# Mixer10_7M.net
KiCad netlist of a schematic drawn in Altium Designer
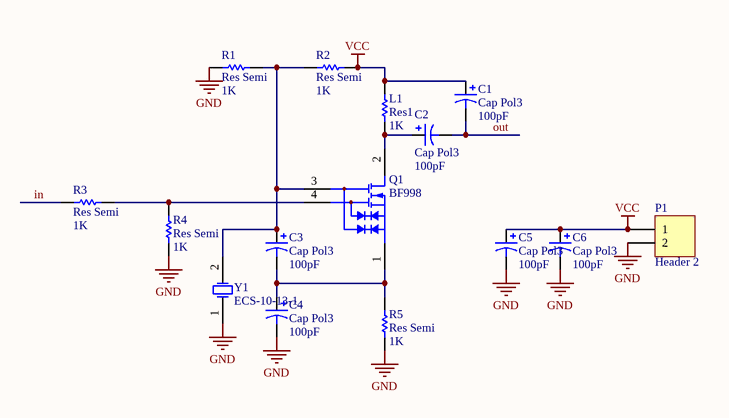
[diagram p0: Mixer10_7M.SchDoc]

(export (version "E")
  (design (tool "Eeschema 10.0.6"))
  (components
    (comp (ref "C1")
      (value "Cap Pol3")
      (footprint "C0805")
      (description "Polarized Capacitor (Surface Mount)")
      (fields (field (name "ALTIUM_VALUE") "100pF") (field (name "PUBLISHER") "Altium Limited"))
      (libsource (lib "Miscellaneous Devices") (part "Cap Pol3"))
    )
    (comp (ref "C2")
      (value "Cap Pol3")
      (footprint "C0805")
      (description "Polarized Capacitor (Surface Mount)")
      (fields (field (name "ALTIUM_VALUE") "100pF") (field (name "PUBLISHER") "Altium Limited"))
      (libsource (lib "Miscellaneous Devices") (part "Cap Pol3"))
    )
    (comp (ref "C3")
      (value "Cap Pol3")
      (footprint "C0805")
      (description "Polarized Capacitor (Surface Mount)")
      (fields (field (name "ALTIUM_VALUE") "100pF") (field (name "PUBLISHER") "Altium Limited"))
      (libsource (lib "Miscellaneous Devices") (part "Cap Pol3"))
    )
    (comp (ref "C4")
      (value "Cap Pol3")
      (footprint "C0805")
      (description "Polarized Capacitor (Surface Mount)")
      (fields (field (name "ALTIUM_VALUE") "100pF") (field (name "PUBLISHER") "Altium Limited"))
      (libsource (lib "Miscellaneous Devices") (part "Cap Pol3"))
    )
    (comp (ref "C5")
      (value "Cap Pol3")
      (footprint "C0805")
      (description "Polarized Capacitor (Surface Mount)")
      (fields (field (name "ALTIUM_VALUE") "100pF") (field (name "PUBLISHER") "Altium Limited"))
      (libsource (lib "Miscellaneous Devices") (part "Cap Pol3"))
    )
    (comp (ref "C6")
      (value "Cap Pol3")
      (footprint "C0805")
      (description "Polarized Capacitor (Surface Mount)")
      (fields (field (name "ALTIUM_VALUE") "100pF") (field (name "PUBLISHER") "Altium Limited"))
      (libsource (lib "Miscellaneous Devices") (part "Cap Pol3"))
    )
    (comp (ref "L1")
      (value "Res1")
      (footprint "AXIAL-0.3")
      (description "Resistor")
      (fields (field (name "ALTIUM_VALUE") "1K") (field (name "PUBLISHER") "Altium Limited"))
      (libsource (lib "Miscellaneous Devices") (part "Res1"))
    )
    (comp (ref "P1")
      (value "Header 2")
      (footprint "HDR1X2")
      (description "Header, 2-Pin")
      (fields (field (name "PUBLISHER") "Altium Limited"))
      (libsource (lib "Miscellaneous Connectors") (part "Header 2"))
    )
    (comp (ref "Q1")
      (value "BF998")
      (footprint "SOT143_N")
      (description "Silicon N-channel Dual-gate MOSFET")
      (fields (field (name "PUBLISHER") "Altium Limited"))
      (libsource (lib "Philips Discrete MOSFET - Low Power") (part "BF998"))
    )
    (comp (ref "R1")
      (value "Res Semi")
      (footprint "2012[0805]")
      (description "Semiconductor Resistor")
      (fields (field (name "ALTIUM_VALUE") "1K") (field (name "PUBLISHER") "Altium Limited"))
      (libsource (lib "Miscellaneous Devices") (part "Res Semi"))
    )
    (comp (ref "R2")
      (value "Res Semi")
      (footprint "2012[0805]")
      (description "Semiconductor Resistor")
      (fields (field (name "ALTIUM_VALUE") "1K") (field (name "PUBLISHER") "Altium Limited"))
      (libsource (lib "Miscellaneous Devices") (part "Res Semi"))
    )
    (comp (ref "R3")
      (value "Res Semi")
      (footprint "2012[0805]")
      (description "Semiconductor Resistor")
      (fields (field (name "ALTIUM_VALUE") "1K") (field (name "PUBLISHER") "Altium Limited"))
      (libsource (lib "Miscellaneous Devices") (part "Res Semi"))
    )
    (comp (ref "R4")
      (value "Res Semi")
      (footprint "2012[0805]")
      (description "Semiconductor Resistor")
      (fields (field (name "ALTIUM_VALUE") "1K") (field (name "PUBLISHER") "Altium Limited"))
      (libsource (lib "Miscellaneous Devices") (part "Res Semi"))
    )
    (comp (ref "R5")
      (value "Res Semi")
      (footprint "2012[0805]")
      (description "Semiconductor Resistor")
      (fields (field (name "ALTIUM_VALUE") "1K") (field (name "PUBLISHER") "Altium Limited"))
      (libsource (lib "Miscellaneous Devices") (part "Res Semi"))
    )
    (comp (ref "Y1")
      (value "ECS-10-13-1")
      (footprint "HC-49U")
      (description "Crystal Oscillator")
      (fields (field (name "PUBLISHER") "Altium Limited"))
      (libsource (lib "ECS Crystal Oscillator") (part "ECS-10-13-1"))
    )
  )
  (nets
    (net (code "1") (name "/in") (class "Default")
      (node (ref "R3") (pin "2") (pinfunction "2_2") (pintype "passive"))
    )
    (net (code "2") (name "/out") (class "Default")
      (node (ref "C1") (pin "2") (pinfunction "2_2") (pintype "passive"))
      (node (ref "C2") (pin "2") (pinfunction "2_2") (pintype "passive"))
    )
    (net (code "3") (name "GND") (class "Default")
      (node (ref "C4") (pin "2") (pinfunction "2_2") (pintype "passive"))
      (node (ref "C5") (pin "2") (pinfunction "2_2") (pintype "passive"))
      (node (ref "C6") (pin "2") (pinfunction "2_2") (pintype "passive"))
      (node (ref "P1") (pin "2") (pinfunction "2_2") (pintype "passive"))
      (node (ref "R1") (pin "1") (pinfunction "1_1") (pintype "passive"))
      (node (ref "R4") (pin "1") (pinfunction "1_1") (pintype "passive"))
      (node (ref "R5") (pin "1") (pinfunction "1_1") (pintype "passive"))
      (node (ref "Y1") (pin "1") (pinfunction "OSC1_1") (pintype "passive"))
    )
    (net (code "4") (name "Net-(Q1-D)") (class "Default")
      (node (ref "C2") (pin "1") (pinfunction "1_1") (pintype "passive"))
      (node (ref "L1") (pin "1") (pinfunction "1_1") (pintype "passive"))
      (node (ref "Q1") (pin "2") (pinfunction "D_2") (pintype "passive"))
    )
    (net (code "5") (name "Net-(Q1-G1)") (class "Default")
      (node (ref "Q1") (pin "4") (pinfunction "G1_4") (pintype "passive"))
      (node (ref "R3") (pin "1") (pinfunction "1_1") (pintype "passive"))
      (node (ref "R4") (pin "2") (pinfunction "2_2") (pintype "passive"))
    )
    (net (code "6") (name "Net-(Q1-G2)") (class "Default")
      (node (ref "C3") (pin "1") (pinfunction "1_1") (pintype "passive"))
      (node (ref "Q1") (pin "3") (pinfunction "G2_3") (pintype "passive"))
      (node (ref "R1") (pin "2") (pinfunction "2_2") (pintype "passive"))
      (node (ref "R2") (pin "1") (pinfunction "1_1") (pintype "passive"))
      (node (ref "Y1") (pin "2") (pinfunction "OSC2_2") (pintype "passive"))
    )
    (net (code "7") (name "Net-(Q1-S)") (class "Default")
      (node (ref "C3") (pin "2") (pinfunction "2_2") (pintype "passive"))
      (node (ref "C4") (pin "1") (pinfunction "1_1") (pintype "passive"))
      (node (ref "Q1") (pin "1") (pinfunction "S_1") (pintype "passive"))
      (node (ref "R5") (pin "2") (pinfunction "2_2") (pintype "passive"))
    )
    (net (code "8") (name "VCC") (class "Default")
      (node (ref "C1") (pin "1") (pinfunction "1_1") (pintype "passive"))
      (node (ref "C5") (pin "1") (pinfunction "1_1") (pintype "passive"))
      (node (ref "C6") (pin "1") (pinfunction "1_1") (pintype "passive"))
      (node (ref "L1") (pin "2") (pinfunction "2_2") (pintype "passive"))
      (node (ref "P1") (pin "1") (pinfunction "1_1") (pintype "passive"))
      (node (ref "R2") (pin "2") (pinfunction "2_2") (pintype "passive"))
    )
  )
)
